# mosfet.net
KiCad netlist of a schematic drawn in Altium Designer
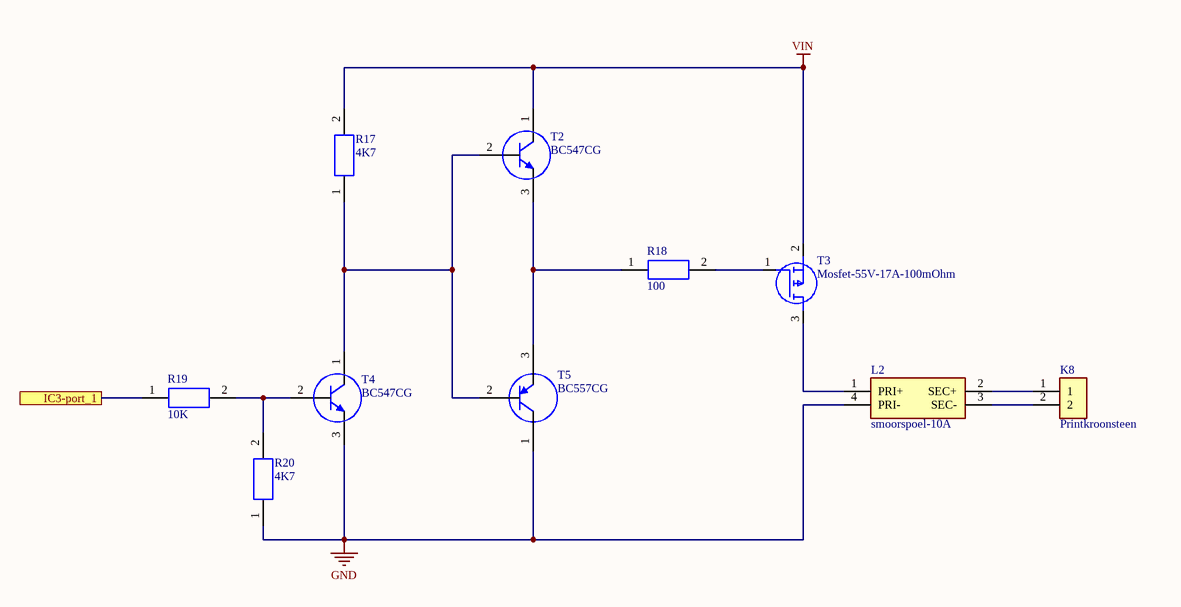
[diagram p0: mosfet.SchDoc]

(export (version "E")
  (design (tool "Eeschema 10.0.6"))
  (components
    (comp (ref "K8")
      (value "Printkroonsteen")
      (footprint "Printkroonsteen")
      (description "Connector")
      (fields
        (field (name "MOUSER2 PART NUMBER") "490-TB007-508-02BE")
        (field (name "MANUFACTURER_PART_NUMBER") "TB007-508-02BE")
      )
      (libsource (lib "project-2022") (part "Printkroonsteen"))
    )
    (comp (ref "L2")
      (value "smoorspoel-10A")
      (footprint "smoorspoel-10A")
      (description "Transformer")
      (fields (field (name "MANUFACTURER_PART_NUMBER") "CM2545X171B-10"))
      (libsource (lib "project-2022") (part "smoorspoel-10A"))
    )
    (comp (ref "R17")
      (value "4K7")
      (footprint "R-0805")
      (description "Resistor")
      (fields (field (name "MANUFACTURER_PART_NUMBER") "TNPU0805500RAZEN00"))
      (libsource (lib "project-2022") (part "R-0805"))
    )
    (comp (ref "R18")
      (value "100")
      (footprint "R-0805")
      (description "Resistor")
      (fields (field (name "MANUFACTURER_PART_NUMBER") "TNPU0805500RAZEN00"))
      (libsource (lib "project-2022") (part "R-0805"))
    )
    (comp (ref "R19")
      (value "10K")
      (footprint "R-0805")
      (description "Resistor")
      (fields (field (name "MANUFACTURER_PART_NUMBER") "TNPU0805500RAZEN00"))
      (libsource (lib "project-2022") (part "R-0805"))
    )
    (comp (ref "R20")
      (value "4K7")
      (footprint "R-0805")
      (description "Resistor")
      (fields (field (name "MANUFACTURER_PART_NUMBER") "TNPU0805500RAZEN00"))
      (libsource (lib "project-2022") (part "R-0805"))
    )
    (comp (ref "T2")
      (value "BC547CG")
      (footprint "BC547C")
      (description "Amplifier Transistor, NPN Silicon, 3-Pin TO-92, Pb-Free, Bulk Box")
      (fields (field (name "MANUFACTURER") "On Semiconductor"))
      (libsource (lib "project-2022") (part "BC547C"))
    )
    (comp (ref "T3")
      (value "Mosfet-55V-17A-100mOhm")
      (footprint "Mosfet-55V-17A-100mOhm")
      (description "MOSFET (P-Channel)")
      (fields
        (field (name "MOUSER2 PART NUMBER") "942-IRF9Z34NPBF")
        (field (name "MANUFACTURER_PART_NUMBER") "IRF9Z34NPBF")
      )
      (libsource (lib "project-2022") (part "Mosfet-55V-17A-100mOhm"))
    )
    (comp (ref "T4")
      (value "BC547CG")
      (footprint "BC547C")
      (description "Amplifier Transistor, NPN Silicon, 3-Pin TO-92, Pb-Free, Bulk Box")
      (fields (field (name "MANUFACTURER") "On Semiconductor"))
      (libsource (lib "project-2022") (part "BC547C"))
    )
    (comp (ref "T5")
      (value "BC557CG")
      (footprint "BC557C")
      (description "Amplifier Transistor, PNP Silicon, 3-Pin TO-92, Pb-Free, Bulk Box")
      (fields (field (name "MANUFACTURER") "On Semiconductor"))
      (libsource (lib "project-2022") (part "BC557C"))
    )
  )
  (nets
    (net (code "1") (name "/IC3-port_1") (class "Default")
      (node (ref "R19") (pin "1") (pinfunction "1_1") (pintype "passive"))
    )
    (net (code "2") (name "GND") (class "Default")
      (node (ref "L2") (pin "4") (pinfunction "PRI-_4") (pintype "passive"))
      (node (ref "R20") (pin "1") (pinfunction "1_1") (pintype "passive"))
      (node (ref "T4") (pin "3") (pinfunction "E_3") (pintype "passive"))
      (node (ref "T5") (pin "1") (pinfunction "C_1") (pintype "passive"))
    )
    (net (code "3") (name "Net-(L2-PRI+)") (class "Default")
      (node (ref "L2") (pin "1") (pinfunction "PRI+_1") (pintype "passive"))
      (node (ref "T3") (pin "3") (pinfunction "D_3") (pintype "passive"))
    )
    (net (code "4") (name "Net-(L2-SEC+)") (class "Default")
      (node (ref "K8") (pin "1") (pinfunction "1_1") (pintype "passive"))
      (node (ref "L2") (pin "2") (pinfunction "SEC+_2") (pintype "passive"))
    )
    (net (code "5") (name "Net-(L2-SEC-)") (class "Default")
      (node (ref "K8") (pin "2") (pinfunction "2_2") (pintype "passive"))
      (node (ref "L2") (pin "3") (pinfunction "SEC-_3") (pintype "passive"))
    )
    (net (code "6") (name "Net-(T2-B)") (class "Default")
      (node (ref "R17") (pin "1") (pinfunction "1_1") (pintype "passive"))
      (node (ref "T2") (pin "2") (pinfunction "B_2") (pintype "passive"))
      (node (ref "T4") (pin "1") (pinfunction "C_1") (pintype "passive"))
      (node (ref "T5") (pin "2") (pinfunction "B_2") (pintype "passive"))
    )
    (net (code "7") (name "Net-(T2-E)") (class "Default")
      (node (ref "R18") (pin "1") (pinfunction "1_1") (pintype "passive"))
      (node (ref "T2") (pin "3") (pinfunction "E_3") (pintype "passive"))
      (node (ref "T5") (pin "3") (pinfunction "E_3") (pintype "passive"))
    )
    (net (code "8") (name "Net-(T3-G)") (class "Default")
      (node (ref "R18") (pin "2") (pinfunction "2_2") (pintype "passive"))
      (node (ref "T3") (pin "1") (pinfunction "G_1") (pintype "passive"))
    )
    (net (code "9") (name "Net-(T4-B)") (class "Default")
      (node (ref "R19") (pin "2") (pinfunction "2_2") (pintype "passive"))
      (node (ref "R20") (pin "2") (pinfunction "2_2") (pintype "passive"))
      (node (ref "T4") (pin "2") (pinfunction "B_2") (pintype "passive"))
    )
    (net (code "10") (name "VIN") (class "Default")
      (node (ref "R17") (pin "2") (pinfunction "2_2") (pintype "passive"))
      (node (ref "T2") (pin "1") (pinfunction "C_1") (pintype "passive"))
      (node (ref "T3") (pin "2") (pinfunction "S_2") (pintype "passive"))
    )
  )
)
